# amt203s_connector.net
KiCad netlist of a schematic drawn in Altium Designer
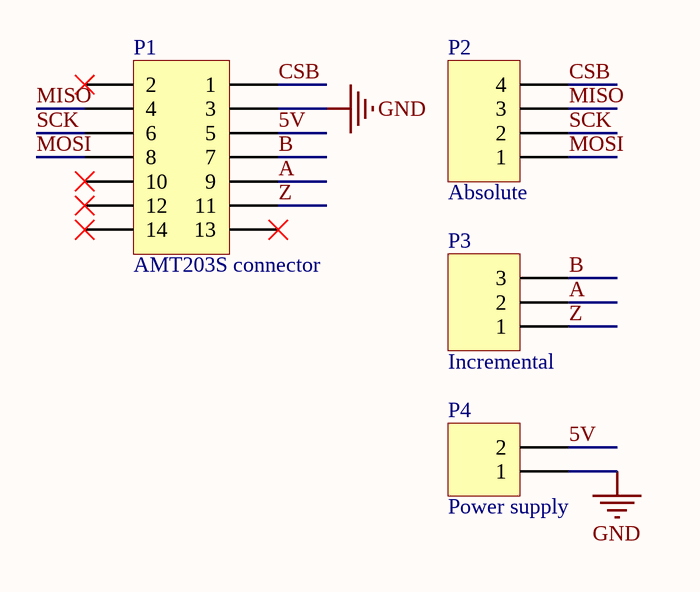
[diagram p0: amt203s_connector.schdoc]

(export (version "E")
  (design (tool "Eeschema 10.0.6"))
  (components
    (comp (ref "P1")
      (value "AMT203S connector")
      (footprint "HDR2X7_1.27mm-AMT203_connector")
      (description "Header, 7-Pin, Dual row")
      (fields (field (name "PUBLISHER") "Altium Limited"))
      (libsource (lib "Miscellaneous Connectors") (part "Header 7X2"))
    )
    (comp (ref "P2")
      (value "Absolute")
      (footprint "HDR1X4")
      (description "Header, 4-Pin")
      (fields (field (name "PUBLISHER") "Altium Limited"))
      (libsource (lib "Miscellaneous Connectors") (part "Header 4"))
    )
    (comp (ref "P3")
      (value "Incremental")
      (footprint "HDR1X3")
      (description "Header, 3-Pin")
      (fields (field (name "PUBLISHER") "Altium Limited"))
      (libsource (lib "Miscellaneous Connectors") (part "Header 3"))
    )
    (comp (ref "P4")
      (value "Power supply")
      (footprint "HDR1X2")
      (description "Header, 2-Pin")
      (fields (field (name "PUBLISHER") "Altium Limited"))
      (libsource (lib "Miscellaneous Connectors") (part "Header 2"))
    )
  )
  (nets
    (net (code "1") (name "/5V") (class "Default")
      (node (ref "P1") (pin "5") (pinfunction "5_5") (pintype "passive"))
      (node (ref "P4") (pin "2") (pinfunction "2_2") (pintype "passive"))
    )
    (net (code "2") (name "/A") (class "Default")
      (node (ref "P1") (pin "9") (pinfunction "9_9") (pintype "passive"))
      (node (ref "P3") (pin "2") (pinfunction "2_2") (pintype "passive"))
    )
    (net (code "3") (name "/B") (class "Default")
      (node (ref "P1") (pin "7") (pinfunction "7_7") (pintype "passive"))
      (node (ref "P3") (pin "3") (pinfunction "3_3") (pintype "passive"))
    )
    (net (code "4") (name "/CSB") (class "Default")
      (node (ref "P1") (pin "1") (pinfunction "1_1") (pintype "passive"))
      (node (ref "P2") (pin "4") (pinfunction "4_4") (pintype "passive"))
    )
    (net (code "5") (name "/MISO") (class "Default")
      (node (ref "P1") (pin "4") (pinfunction "4_4") (pintype "passive"))
      (node (ref "P2") (pin "3") (pinfunction "3_3") (pintype "passive"))
    )
    (net (code "6") (name "/MOSI") (class "Default")
      (node (ref "P1") (pin "8") (pinfunction "8_8") (pintype "passive"))
      (node (ref "P2") (pin "1") (pinfunction "1_1") (pintype "passive"))
    )
    (net (code "7") (name "/SCK") (class "Default")
      (node (ref "P1") (pin "6") (pinfunction "6_6") (pintype "passive"))
      (node (ref "P2") (pin "2") (pinfunction "2_2") (pintype "passive"))
    )
    (net (code "8") (name "/Z") (class "Default")
      (node (ref "P1") (pin "11") (pinfunction "11_11") (pintype "passive"))
      (node (ref "P3") (pin "1") (pinfunction "1_1") (pintype "passive"))
    )
    (net (code "9") (name "GND") (class "Default")
      (node (ref "P1") (pin "3") (pinfunction "3_3") (pintype "passive"))
      (node (ref "P4") (pin "1") (pinfunction "1_1") (pintype "passive"))
    )
    (net (code "10") (name "unconnected-(P1-Pad2)") (class "Default")
      (node (ref "P1") (pin "2") (pinfunction "2_2") (pintype "passive+no_connect"))
    )
    (net (code "11") (name "unconnected-(P1-Pad10)") (class "Default")
      (node (ref "P1") (pin "10") (pinfunction "10_10") (pintype "passive+no_connect"))
    )
    (net (code "12") (name "unconnected-(P1-Pad12)") (class "Default")
      (node (ref "P1") (pin "12") (pinfunction "12_12") (pintype "passive+no_connect"))
    )
    (net (code "13") (name "unconnected-(P1-Pad13)") (class "Default")
      (node (ref "P1") (pin "13") (pinfunction "13_13") (pintype "passive+no_connect"))
    )
    (net (code "14") (name "unconnected-(P1-Pad14)") (class "Default")
      (node (ref "P1") (pin "14") (pinfunction "14_14") (pintype "passive+no_connect"))
    )
  )
)
